# PSU_Schematic.net
KiCad netlist of a schematic drawn in Altium Designer
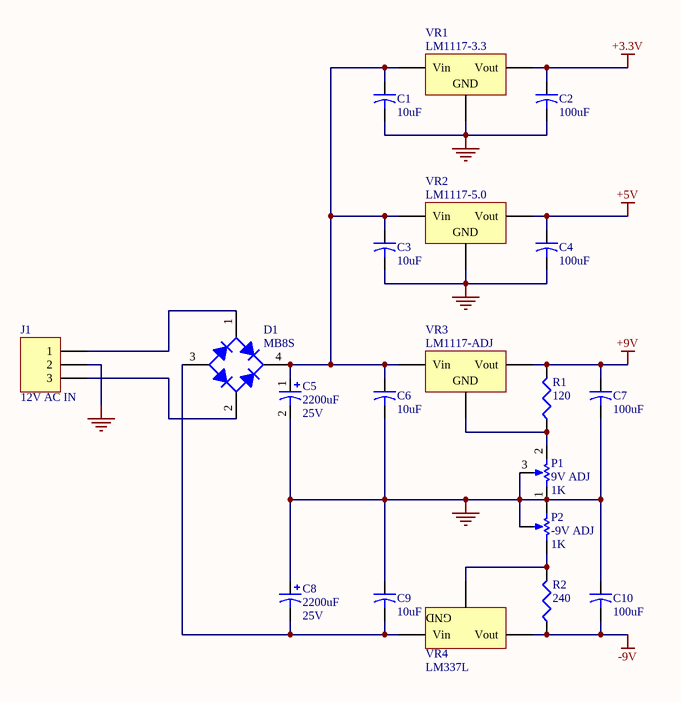
[diagram p0: PSU.Schematic.SchDoc]

(export (version "E")
  (design (tool "Eeschema 10.0.6"))
  (components
    (comp (ref "C1")
      (value "10uF")
      (footprint "CAPC1608N")
      (description "Capacitor")
      (fields (field (name "PUBLISHER") "Altium Limited"))
      (libsource (lib "Miscellaneous Devices") (part "Cap2"))
    )
    (comp (ref "C2")
      (value "100uF")
      (footprint "CAPC1608N")
      (description "Capacitor")
      (fields (field (name "PUBLISHER") "Altium Limited"))
      (libsource (lib "Miscellaneous Devices") (part "Cap2"))
    )
    (comp (ref "C3")
      (value "10uF")
      (footprint "CAPC1608N")
      (description "Capacitor")
      (fields (field (name "PUBLISHER") "Altium Limited"))
      (libsource (lib "Miscellaneous Devices") (part "Cap2"))
    )
    (comp (ref "C4")
      (value "100uF")
      (footprint "CAPC1608N")
      (description "Capacitor")
      (fields (field (name "PUBLISHER") "Altium Limited"))
      (libsource (lib "Miscellaneous Devices") (part "Cap2"))
    )
    (comp (ref "C5")
      (value "2200uF")
      (footprint "Condo electro 13")
      (description "Polarized Capacitor (Radial)")
      (fields (field (name "ALTIUM_VALUE") "25V") (field (name "PUBLISHER") "Altium Limited"))
      (libsource (lib "") (part "Cap Pol1_1"))
    )
    (comp (ref "C6")
      (value "10uF")
      (footprint "CAPC1608N")
      (description "Capacitor")
      (fields (field (name "PUBLISHER") "Altium Limited"))
      (libsource (lib "Miscellaneous Devices") (part "Cap2"))
    )
    (comp (ref "C7")
      (value "100uF")
      (footprint "CAPC1608N")
      (description "Capacitor")
      (fields (field (name "PUBLISHER") "Altium Limited"))
      (libsource (lib "Miscellaneous Devices") (part "Cap2"))
    )
    (comp (ref "C8")
      (value "2200uF")
      (footprint "Condo electro 13")
      (description "Polarized Capacitor (Radial)")
      (fields (field (name "ALTIUM_VALUE") "25V") (field (name "PUBLISHER") "Altium Limited"))
      (libsource (lib "Miscellaneous Devices") (part "Cap Pol1"))
    )
    (comp (ref "C9")
      (value "10uF")
      (footprint "CAPC1608N")
      (description "Capacitor")
      (fields (field (name "PUBLISHER") "Altium Limited"))
      (libsource (lib "Miscellaneous Devices") (part "Cap2"))
    )
    (comp (ref "C10")
      (value "100uF")
      (footprint "CAPC1608N")
      (description "Capacitor")
      (fields (field (name "PUBLISHER") "Altium Limited"))
      (libsource (lib "Miscellaneous Devices") (part "Cap2"))
    )
    (comp (ref "D1")
      (value "MB8S")
      (footprint "MB8S")
      (description "Full Wave Diode Bridge")
      (fields (field (name "PUBLISHER") "Altium Limited"))
      (libsource (lib "Miscellaneous Devices") (part "Bridge1"))
    )
    (comp (ref "J1")
      (value "12V AC IN")
      (footprint "HDR1X3")
      (description "Header, 3-Pin")
      (fields (field (name "PUBLISHER") "Altium Limited"))
      (libsource (lib "Miscellaneous Connectors") (part "Header 3"))
    )
    (comp (ref "P1")
      (value "9V ADJ")
      (footprint "BOURNS Trim pot")
      (description "Potentiometer")
      (fields (field (name "ALTIUM_VALUE") "1K") (field (name "PUBLISHER") "Altium Limited"))
      (libsource (lib "Miscellaneous Devices") (part "RPot"))
    )
    (comp (ref "P2")
      (value "-9V ADJ")
      (footprint "BOURNS Trim pot")
      (description "Potentiometer")
      (fields (field (name "ALTIUM_VALUE") "1K") (field (name "PUBLISHER") "Altium Limited"))
      (libsource (lib "") (part "RPot_1"))
    )
    (comp (ref "R1")
      (value "120")
      (footprint "CAPC1608N")
      (description "Resistor")
      (fields (field (name "PUBLISHER") "Altium Limited"))
      (libsource (lib "Miscellaneous Devices") (part "Res3"))
    )
    (comp (ref "R2")
      (value "240")
      (footprint "CAPC1608N")
      (description "Resistor")
      (fields (field (name "PUBLISHER") "Altium Limited"))
      (libsource (lib "Miscellaneous Devices") (part "Res3"))
    )
    (comp (ref "VR1")
      (value "LM1117-3.3")
      (footprint "LM1117-SOT")
      (description "Voltage Regulator")
      (fields (field (name "PUBLISHER") "Altium Limited"))
      (libsource (lib "Miscellaneous Devices") (part "Volt Reg"))
    )
    (comp (ref "VR2")
      (value "LM1117-5.0")
      (footprint "LM1117-SOT")
      (description "Voltage Regulator")
      (fields (field (name "PUBLISHER") "Altium Limited"))
      (libsource (lib "Miscellaneous Devices") (part "Volt Reg"))
    )
    (comp (ref "VR3")
      (value "LM1117-ADJ")
      (footprint "LM1117-SOT")
      (description "Voltage Regulator")
      (fields (field (name "PUBLISHER") "Altium Limited"))
      (libsource (lib "Miscellaneous Devices") (part "Volt Reg"))
    )
    (comp (ref "VR4")
      (value "LM337L")
      (footprint "LM337L")
      (description "Voltage Regulator")
      (fields (field (name "PUBLISHER") "Altium Limited"))
      (libsource (lib "") (part "Volt Reg_1"))
    )
  )
  (nets
    (net (code "1") (name "+3.3V") (class "Default")
      (node (ref "C2") (pin "1") (pinfunction "1_1") (pintype "passive"))
      (node (ref "VR1") (pin "3") (pinfunction "Vout_3") (pintype "passive"))
    )
    (net (code "2") (name "+5V") (class "Default")
      (node (ref "C4") (pin "1") (pinfunction "1_1") (pintype "passive"))
      (node (ref "VR2") (pin "3") (pinfunction "Vout_3") (pintype "passive"))
    )
    (net (code "3") (name "+9V") (class "Default")
      (node (ref "C7") (pin "1") (pinfunction "1_1") (pintype "passive"))
      (node (ref "R1") (pin "2") (pinfunction "2_2") (pintype "passive"))
      (node (ref "VR3") (pin "3") (pinfunction "Vout_3") (pintype "passive"))
    )
    (net (code "4") (name "-9V") (class "Default")
      (node (ref "C10") (pin "2") (pinfunction "2_2") (pintype "passive"))
      (node (ref "R2") (pin "1") (pinfunction "1_1") (pintype "passive"))
      (node (ref "VR4") (pin "3") (pinfunction "Vout_3") (pintype "passive"))
    )
    (net (code "5") (name "GND") (class "Default")
      (node (ref "C1") (pin "2") (pinfunction "2_2") (pintype "passive"))
      (node (ref "C10") (pin "1") (pinfunction "1_1") (pintype "passive"))
      (node (ref "C2") (pin "2") (pinfunction "2_2") (pintype "passive"))
      (node (ref "C3") (pin "2") (pinfunction "2_2") (pintype "passive"))
      (node (ref "C4") (pin "2") (pinfunction "2_2") (pintype "passive"))
      (node (ref "C5") (pin "2") (pinfunction "2_2") (pintype "passive"))
      (node (ref "C6") (pin "2") (pinfunction "2_2") (pintype "passive"))
      (node (ref "C7") (pin "2") (pinfunction "2_2") (pintype "passive"))
      (node (ref "C8") (pin "1") (pinfunction "1_1") (pintype "passive"))
      (node (ref "C9") (pin "1") (pinfunction "1_1") (pintype "passive"))
      (node (ref "J1") (pin "2") (pinfunction "2_2") (pintype "passive"))
      (node (ref "P1") (pin "1") (pinfunction "TOP_1") (pintype "passive"))
      (node (ref "P1") (pin "3") (pinfunction "TAP_3") (pintype "passive"))
      (node (ref "P2") (pin "2") (pinfunction "BOT_2") (pintype "passive"))
      (node (ref "P2") (pin "3") (pinfunction "TAP_3") (pintype "passive"))
      (node (ref "VR1") (pin "2") (pinfunction "GND_2") (pintype "passive"))
      (node (ref "VR2") (pin "2") (pinfunction "GND_2") (pintype "passive"))
    )
    (net (code "6") (name "Net-(D1-A)") (class "Default")
      (node (ref "C8") (pin "2") (pinfunction "2_2") (pintype "passive"))
      (node (ref "C9") (pin "2") (pinfunction "2_2") (pintype "passive"))
      (node (ref "D1") (pin "3") (pinfunction "A_3") (pintype "passive"))
      (node (ref "VR4") (pin "1") (pinfunction "Vin_1") (pintype "passive"))
    )
    (net (code "7") (name "Net-(D1-C-Pad1)") (class "Default")
      (node (ref "D1") (pin "1") (pinfunction "C_1") (pintype "passive"))
      (node (ref "J1") (pin "1") (pinfunction "1_1") (pintype "passive"))
    )
    (net (code "8") (name "Net-(D1-C-Pad2)") (class "Default")
      (node (ref "D1") (pin "2") (pinfunction "C_2") (pintype "passive"))
      (node (ref "J1") (pin "3") (pinfunction "3_3") (pintype "passive"))
    )
    (net (code "9") (name "Net-(D1-K)") (class "Default")
      (node (ref "C1") (pin "1") (pinfunction "1_1") (pintype "passive"))
      (node (ref "C3") (pin "1") (pinfunction "1_1") (pintype "passive"))
      (node (ref "C5") (pin "1") (pinfunction "1_1") (pintype "passive"))
      (node (ref "C6") (pin "1") (pinfunction "1_1") (pintype "passive"))
      (node (ref "D1") (pin "4") (pinfunction "K_4") (pintype "passive"))
      (node (ref "VR1") (pin "1") (pinfunction "Vin_1") (pintype "passive"))
      (node (ref "VR2") (pin "1") (pinfunction "Vin_1") (pintype "passive"))
      (node (ref "VR3") (pin "1") (pinfunction "Vin_1") (pintype "passive"))
    )
    (net (code "10") (name "Net-(P1-BOT)") (class "Default")
      (node (ref "P1") (pin "2") (pinfunction "BOT_2") (pintype "passive"))
      (node (ref "R1") (pin "1") (pinfunction "1_1") (pintype "passive"))
      (node (ref "VR3") (pin "2") (pinfunction "GND_2") (pintype "passive"))
    )
    (net (code "11") (name "Net-(P2-TOP)") (class "Default")
      (node (ref "P2") (pin "1") (pinfunction "TOP_1") (pintype "passive"))
      (node (ref "R2") (pin "2") (pinfunction "2_2") (pintype "passive"))
      (node (ref "VR4") (pin "2") (pinfunction "ADJ_2") (pintype "passive"))
    )
  )
)
